# 4017Divider.net
KiCad netlist of a schematic drawn in EAGLE
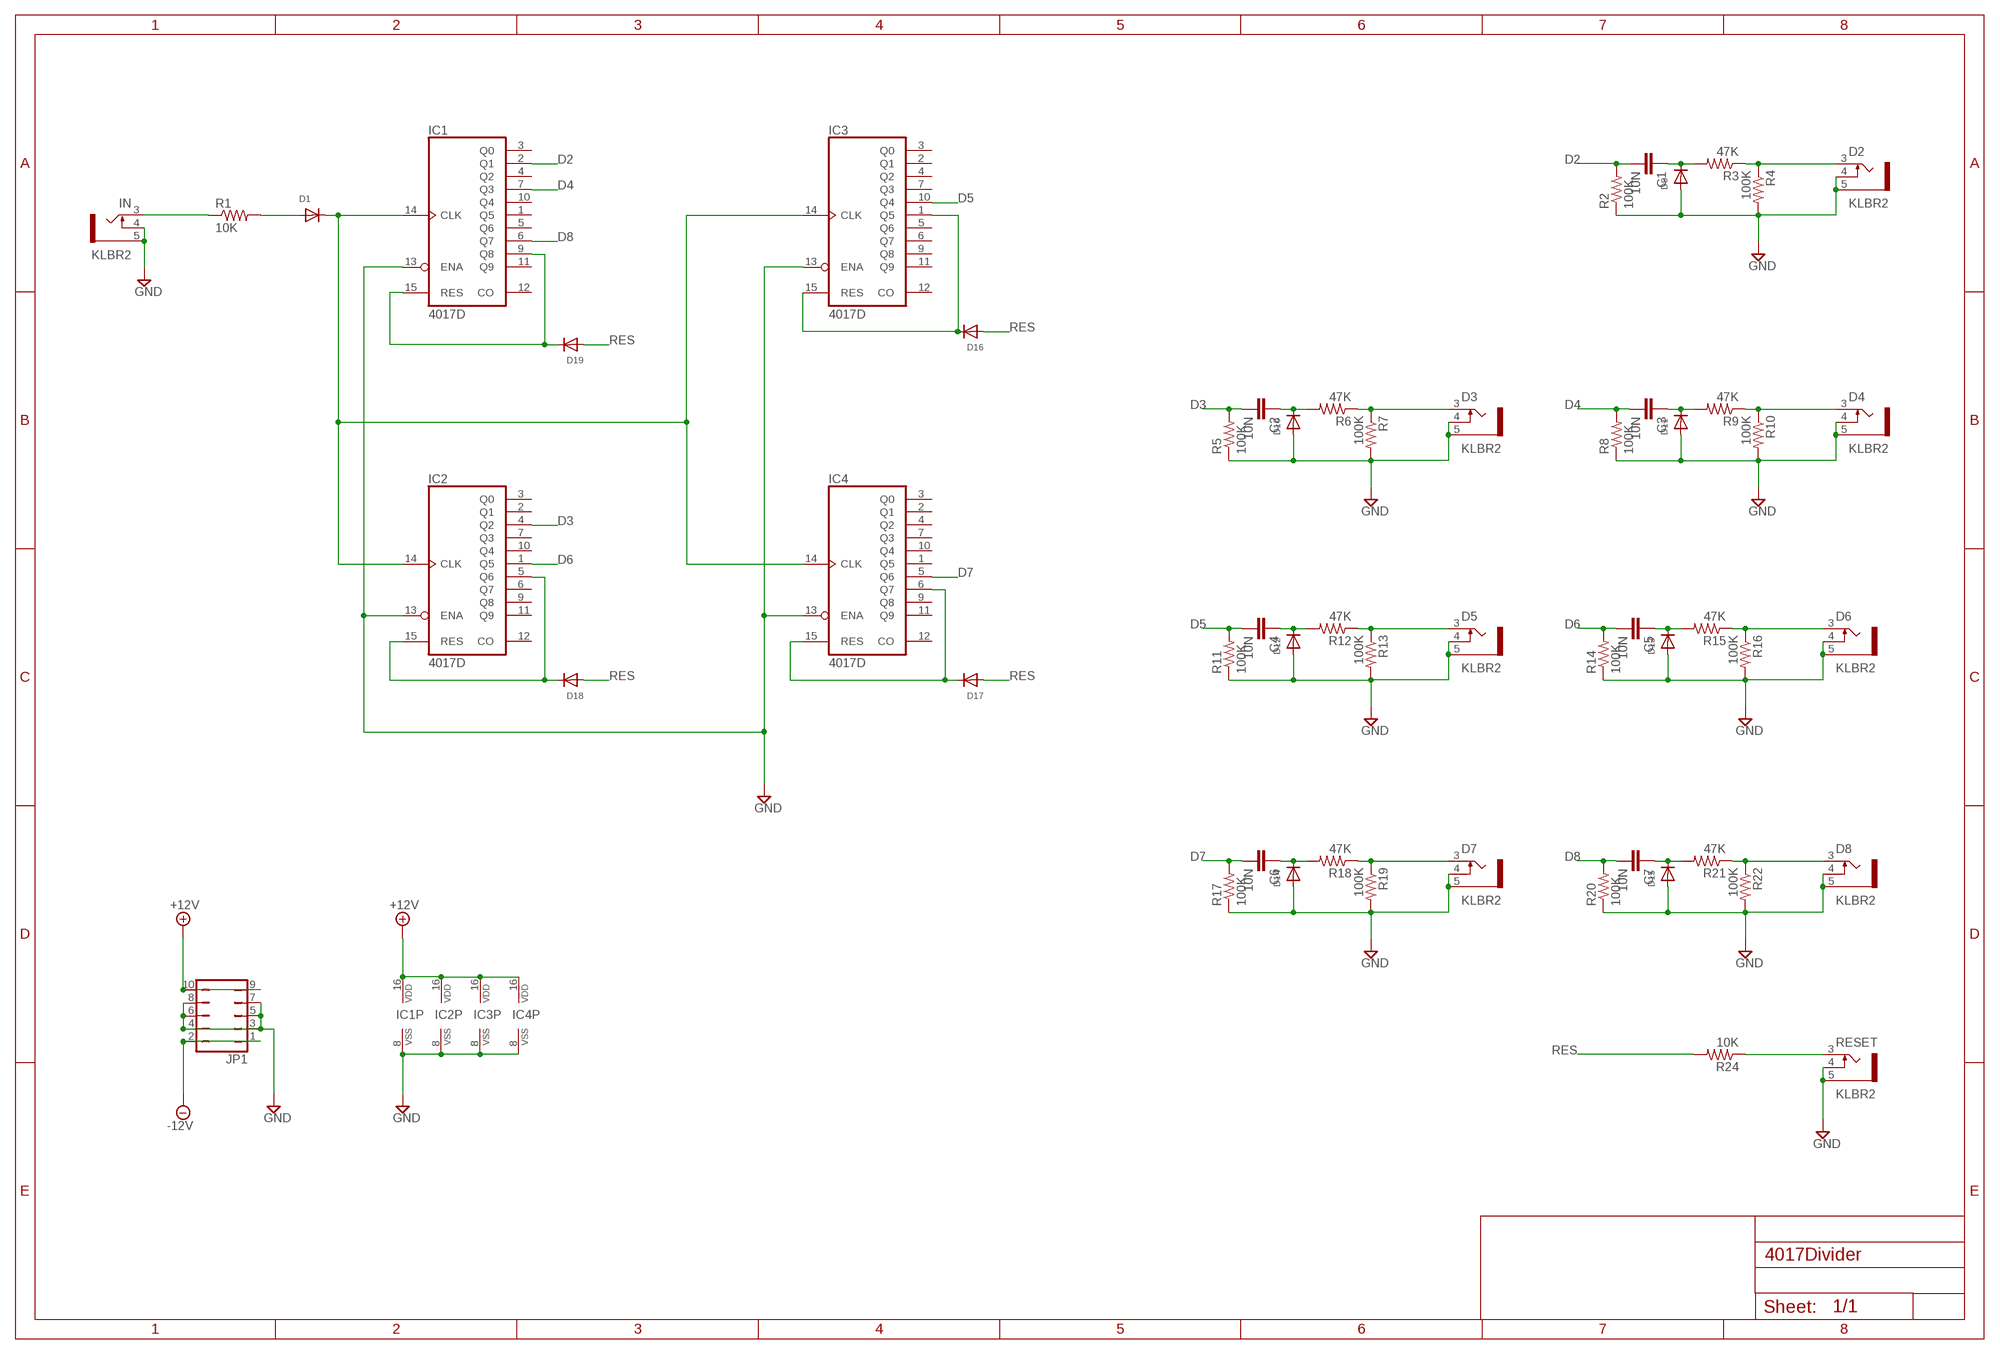
[diagram p0: schematic, sheet 1]

(export (version "E")
  (design (tool "Eeschema 10.0.6"))
  (components
    (comp (ref "C1")
      (value "10N")
      (footprint "eagle-import:C0603K")
      (libsource (lib "eagle-import") (part "C-EUC0603K"))
    )
    (comp (ref "C2")
      (value "10N")
      (footprint "eagle-import:C0603K")
      (libsource (lib "eagle-import") (part "C-EUC0603K"))
    )
    (comp (ref "C3")
      (value "10N")
      (footprint "eagle-import:C0603K")
      (libsource (lib "eagle-import") (part "C-EUC0603K"))
    )
    (comp (ref "C4")
      (value "10N")
      (footprint "eagle-import:C0603K")
      (libsource (lib "eagle-import") (part "C-EUC0603K"))
    )
    (comp (ref "C5")
      (value "10N")
      (footprint "eagle-import:C0603K")
      (libsource (lib "eagle-import") (part "C-EUC0603K"))
    )
    (comp (ref "C6")
      (value "10N")
      (footprint "eagle-import:C0603K")
      (libsource (lib "eagle-import") (part "C-EUC0603K"))
    )
    (comp (ref "C7")
      (value "10N")
      (footprint "eagle-import:C0603K")
      (libsource (lib "eagle-import") (part "C-EUC0603K"))
    )
    (comp (ref "D1")
      (value "DIODESOD-123")
      (footprint "eagle-import:SOD-123")
      (libsource (lib "eagle-import") (part "DIODESOD-123"))
    )
    (comp (ref "D2")
      (value "KLBR2")
      (footprint "eagle-import:KLBR2")
      (libsource (lib "eagle-import") (part "KLBR?2"))
    )
    (comp (ref "D3")
      (value "KLBR2")
      (footprint "eagle-import:KLBR2")
      (libsource (lib "eagle-import") (part "KLBR?2"))
    )
    (comp (ref "D4")
      (value "KLBR2")
      (footprint "eagle-import:KLBR2")
      (libsource (lib "eagle-import") (part "KLBR?2"))
    )
    (comp (ref "D5")
      (value "KLBR2")
      (footprint "eagle-import:KLBR2")
      (libsource (lib "eagle-import") (part "KLBR?2"))
    )
    (comp (ref "D6")
      (value "KLBR2")
      (footprint "eagle-import:KLBR2")
      (libsource (lib "eagle-import") (part "KLBR?2"))
    )
    (comp (ref "D7")
      (value "KLBR2")
      (footprint "eagle-import:KLBR2")
      (libsource (lib "eagle-import") (part "KLBR?2"))
    )
    (comp (ref "D8")
      (value "KLBR2")
      (footprint "eagle-import:KLBR2")
      (libsource (lib "eagle-import") (part "KLBR?2"))
    )
    (comp (ref "D9")
      (value "DIODESOD-123")
      (footprint "eagle-import:SOD-123")
      (libsource (lib "eagle-import") (part "DIODESOD-123"))
    )
    (comp (ref "D10")
      (value "DIODESOD-123")
      (footprint "eagle-import:SOD-123")
      (libsource (lib "eagle-import") (part "DIODESOD-123"))
    )
    (comp (ref "D11")
      (value "DIODESOD-123")
      (footprint "eagle-import:SOD-123")
      (libsource (lib "eagle-import") (part "DIODESOD-123"))
    )
    (comp (ref "D12")
      (value "DIODESOD-123")
      (footprint "eagle-import:SOD-123")
      (libsource (lib "eagle-import") (part "DIODESOD-123"))
    )
    (comp (ref "D13")
      (value "DIODESOD-123")
      (footprint "eagle-import:SOD-123")
      (libsource (lib "eagle-import") (part "DIODESOD-123"))
    )
    (comp (ref "D14")
      (value "DIODESOD-123")
      (footprint "eagle-import:SOD-123")
      (libsource (lib "eagle-import") (part "DIODESOD-123"))
    )
    (comp (ref "D15")
      (value "DIODESOD-123")
      (footprint "eagle-import:SOD-123")
      (libsource (lib "eagle-import") (part "DIODESOD-123"))
    )
    (comp (ref "D16")
      (value "DIODESOD-123")
      (footprint "eagle-import:SOD-123")
      (libsource (lib "eagle-import") (part "DIODESOD-123"))
    )
    (comp (ref "D17")
      (value "DIODESOD-123")
      (footprint "eagle-import:SOD-123")
      (libsource (lib "eagle-import") (part "DIODESOD-123"))
    )
    (comp (ref "D18")
      (value "DIODESOD-123")
      (footprint "eagle-import:SOD-123")
      (libsource (lib "eagle-import") (part "DIODESOD-123"))
    )
    (comp (ref "D19")
      (value "DIODESOD-123")
      (footprint "eagle-import:SOD-123")
      (libsource (lib "eagle-import") (part "DIODESOD-123"))
    )
    (comp (ref "IC1")
      (value "4017D")
      (footprint "eagle-import:SO16")
      (libsource (lib "eagle-import") (part "4017D"))
    )
    (comp (ref "IC2")
      (value "4017D")
      (footprint "eagle-import:SO16")
      (libsource (lib "eagle-import") (part "4017D"))
    )
    (comp (ref "IC3")
      (value "4017D")
      (footprint "eagle-import:SO16")
      (libsource (lib "eagle-import") (part "4017D"))
    )
    (comp (ref "IC4")
      (value "4017D")
      (footprint "eagle-import:SO16")
      (libsource (lib "eagle-import") (part "4017D"))
    )
    (comp (ref "IN")
      (value "KLBR2")
      (footprint "eagle-import:KLBR2")
      (libsource (lib "eagle-import") (part "KLBR?2"))
    )
    (comp (ref "JP1")
      (value "JP5Q")
      (footprint "eagle-import:JP5Q")
      (libsource (lib "eagle-import") (part "JP5Q"))
    )
    (comp (ref "R1")
      (value "10K")
      (footprint "eagle-import:R0603")
      (libsource (lib "eagle-import") (part "R-US_R0603"))
    )
    (comp (ref "R2")
      (value "100K")
      (footprint "eagle-import:R0603")
      (libsource (lib "eagle-import") (part "R-US_R0603"))
    )
    (comp (ref "R3")
      (value "47K")
      (footprint "eagle-import:R0603")
      (libsource (lib "eagle-import") (part "R-US_R0603"))
    )
    (comp (ref "R4")
      (value "100K")
      (footprint "eagle-import:R0603")
      (libsource (lib "eagle-import") (part "R-US_R0603"))
    )
    (comp (ref "R5")
      (value "100K")
      (footprint "eagle-import:R0603")
      (libsource (lib "eagle-import") (part "R-US_R0603"))
    )
    (comp (ref "R6")
      (value "47K")
      (footprint "eagle-import:R0603")
      (libsource (lib "eagle-import") (part "R-US_R0603"))
    )
    (comp (ref "R7")
      (value "100K")
      (footprint "eagle-import:R0603")
      (libsource (lib "eagle-import") (part "R-US_R0603"))
    )
    (comp (ref "R8")
      (value "100K")
      (footprint "eagle-import:R0603")
      (libsource (lib "eagle-import") (part "R-US_R0603"))
    )
    (comp (ref "R9")
      (value "47K")
      (footprint "eagle-import:R0603")
      (libsource (lib "eagle-import") (part "R-US_R0603"))
    )
    (comp (ref "R10")
      (value "100K")
      (footprint "eagle-import:R0603")
      (libsource (lib "eagle-import") (part "R-US_R0603"))
    )
    (comp (ref "R11")
      (value "100K")
      (footprint "eagle-import:R0603")
      (libsource (lib "eagle-import") (part "R-US_R0603"))
    )
    (comp (ref "R12")
      (value "47K")
      (footprint "eagle-import:R0603")
      (libsource (lib "eagle-import") (part "R-US_R0603"))
    )
    (comp (ref "R13")
      (value "100K")
      (footprint "eagle-import:R0603")
      (libsource (lib "eagle-import") (part "R-US_R0603"))
    )
    (comp (ref "R14")
      (value "100K")
      (footprint "eagle-import:R0603")
      (libsource (lib "eagle-import") (part "R-US_R0603"))
    )
    (comp (ref "R15")
      (value "47K")
      (footprint "eagle-import:R0603")
      (libsource (lib "eagle-import") (part "R-US_R0603"))
    )
    (comp (ref "R16")
      (value "100K")
      (footprint "eagle-import:R0603")
      (libsource (lib "eagle-import") (part "R-US_R0603"))
    )
    (comp (ref "R17")
      (value "100K")
      (footprint "eagle-import:R0603")
      (libsource (lib "eagle-import") (part "R-US_R0603"))
    )
    (comp (ref "R18")
      (value "47K")
      (footprint "eagle-import:R0603")
      (libsource (lib "eagle-import") (part "R-US_R0603"))
    )
    (comp (ref "R19")
      (value "100K")
      (footprint "eagle-import:R0603")
      (libsource (lib "eagle-import") (part "R-US_R0603"))
    )
    (comp (ref "R20")
      (value "100K")
      (footprint "eagle-import:R0603")
      (libsource (lib "eagle-import") (part "R-US_R0603"))
    )
    (comp (ref "R21")
      (value "47K")
      (footprint "eagle-import:R0603")
      (libsource (lib "eagle-import") (part "R-US_R0603"))
    )
    (comp (ref "R22")
      (value "100K")
      (footprint "eagle-import:R0603")
      (libsource (lib "eagle-import") (part "R-US_R0603"))
    )
    (comp (ref "R24")
      (value "10K")
      (footprint "eagle-import:R0603")
      (libsource (lib "eagle-import") (part "R-US_R0603"))
    )
    (comp (ref "RESET")
      (value "KLBR2")
      (footprint "eagle-import:KLBR2")
      (libsource (lib "eagle-import") (part "KLBR?2"))
    )
  )
  (nets
    (net (code "1") (name "+12V") (class "Default")
      (node (ref "IC1") (pin "16") (pinfunction "VDD_16") (pintype "power_in"))
      (node (ref "IC2") (pin "16") (pinfunction "VDD_16") (pintype "power_in"))
      (node (ref "IC3") (pin "16") (pinfunction "VDD_16") (pintype "power_in"))
      (node (ref "IC4") (pin "16") (pinfunction "VDD_16") (pintype "power_in"))
      (node (ref "JP1") (pin "10") (pinfunction "10_10") (pintype "passive"))
      (node (ref "JP1") (pin "9") (pinfunction "9_9") (pintype "passive"))
    )
    (net (code "2") (name "-12V") (class "Default")
      (node (ref "JP1") (pin "1") (pinfunction "1_1") (pintype "passive"))
      (node (ref "JP1") (pin "2") (pinfunction "2_2") (pintype "passive"))
    )
    (net (code "3") (name "/D2") (class "Default")
      (node (ref "C1") (pin "2") (pinfunction "2_2") (pintype "passive"))
      (node (ref "IC1") (pin "2") (pinfunction "Q1_2") (pintype "output"))
      (node (ref "R2") (pin "2") (pinfunction "2_2") (pintype "passive"))
    )
    (net (code "4") (name "/D3") (class "Default")
      (node (ref "C2") (pin "2") (pinfunction "2_2") (pintype "passive"))
      (node (ref "IC2") (pin "4") (pinfunction "Q2_4") (pintype "output"))
      (node (ref "R5") (pin "2") (pinfunction "2_2") (pintype "passive"))
    )
    (net (code "5") (name "/D4") (class "Default")
      (node (ref "C3") (pin "2") (pinfunction "2_2") (pintype "passive"))
      (node (ref "IC1") (pin "7") (pinfunction "Q3_7") (pintype "output"))
      (node (ref "R8") (pin "2") (pinfunction "2_2") (pintype "passive"))
    )
    (net (code "6") (name "/D5") (class "Default")
      (node (ref "C4") (pin "2") (pinfunction "2_2") (pintype "passive"))
      (node (ref "IC3") (pin "10") (pinfunction "Q4_10") (pintype "output"))
      (node (ref "R11") (pin "2") (pinfunction "2_2") (pintype "passive"))
    )
    (net (code "7") (name "/D6") (class "Default")
      (node (ref "C5") (pin "2") (pinfunction "2_2") (pintype "passive"))
      (node (ref "IC2") (pin "1") (pinfunction "Q5_1") (pintype "output"))
      (node (ref "R14") (pin "2") (pinfunction "2_2") (pintype "passive"))
    )
    (net (code "8") (name "/D7") (class "Default")
      (node (ref "C6") (pin "2") (pinfunction "2_2") (pintype "passive"))
      (node (ref "IC4") (pin "5") (pinfunction "Q6_5") (pintype "output"))
      (node (ref "R17") (pin "2") (pinfunction "2_2") (pintype "passive"))
    )
    (net (code "9") (name "/D8") (class "Default")
      (node (ref "C7") (pin "2") (pinfunction "2_2") (pintype "passive"))
      (node (ref "IC1") (pin "6") (pinfunction "Q7_6") (pintype "output"))
      (node (ref "R20") (pin "2") (pinfunction "2_2") (pintype "passive"))
    )
    (net (code "10") (name "/RES") (class "Default")
      (node (ref "D16") (pin "A") (pinfunction "A_A") (pintype "passive"))
      (node (ref "D17") (pin "A") (pinfunction "A_A") (pintype "passive"))
      (node (ref "D18") (pin "A") (pinfunction "A_A") (pintype "passive"))
      (node (ref "D19") (pin "A") (pinfunction "A_A") (pintype "passive"))
      (node (ref "R24") (pin "2") (pinfunction "2_2") (pintype "passive"))
    )
    (net (code "11") (name "GND") (class "Default")
      (node (ref "D10") (pin "A") (pinfunction "A_A") (pintype "passive"))
      (node (ref "D11") (pin "A") (pinfunction "A_A") (pintype "passive"))
      (node (ref "D12") (pin "A") (pinfunction "A_A") (pintype "passive"))
      (node (ref "D13") (pin "A") (pinfunction "A_A") (pintype "passive"))
      (node (ref "D14") (pin "A") (pinfunction "A_A") (pintype "passive"))
      (node (ref "D15") (pin "A") (pinfunction "A_A") (pintype "passive"))
      (node (ref "D2") (pin "4") (pinfunction "4_4") (pintype "passive"))
      (node (ref "D2") (pin "5") (pinfunction "5_5") (pintype "passive"))
      (node (ref "D3") (pin "4") (pinfunction "4_4") (pintype "passive"))
      (node (ref "D3") (pin "5") (pinfunction "5_5") (pintype "passive"))
      (node (ref "D4") (pin "4") (pinfunction "4_4") (pintype "passive"))
      (node (ref "D4") (pin "5") (pinfunction "5_5") (pintype "passive"))
      (node (ref "D5") (pin "4") (pinfunction "4_4") (pintype "passive"))
      (node (ref "D5") (pin "5") (pinfunction "5_5") (pintype "passive"))
      (node (ref "D6") (pin "4") (pinfunction "4_4") (pintype "passive"))
      (node (ref "D6") (pin "5") (pinfunction "5_5") (pintype "passive"))
      (node (ref "D7") (pin "4") (pinfunction "4_4") (pintype "passive"))
      (node (ref "D7") (pin "5") (pinfunction "5_5") (pintype "passive"))
      (node (ref "D8") (pin "4") (pinfunction "4_4") (pintype "passive"))
      (node (ref "D8") (pin "5") (pinfunction "5_5") (pintype "passive"))
      (node (ref "D9") (pin "A") (pinfunction "A_A") (pintype "passive"))
      (node (ref "IC1") (pin "13") (pinfunction "ENA_13") (pintype "input"))
      (node (ref "IC1") (pin "8") (pinfunction "VSS_8") (pintype "power_in"))
      (node (ref "IC2") (pin "13") (pinfunction "ENA_13") (pintype "input"))
      (node (ref "IC2") (pin "8") (pinfunction "VSS_8") (pintype "power_in"))
      (node (ref "IC3") (pin "13") (pinfunction "ENA_13") (pintype "input"))
      (node (ref "IC3") (pin "8") (pinfunction "VSS_8") (pintype "power_in"))
      (node (ref "IC4") (pin "13") (pinfunction "ENA_13") (pintype "input"))
      (node (ref "IC4") (pin "8") (pinfunction "VSS_8") (pintype "power_in"))
      (node (ref "IN") (pin "4") (pinfunction "4_4") (pintype "passive"))
      (node (ref "IN") (pin "5") (pinfunction "5_5") (pintype "passive"))
      (node (ref "JP1") (pin "3") (pinfunction "3_3") (pintype "passive"))
      (node (ref "JP1") (pin "4") (pinfunction "4_4") (pintype "passive"))
      (node (ref "JP1") (pin "5") (pinfunction "5_5") (pintype "passive"))
      (node (ref "JP1") (pin "6") (pinfunction "6_6") (pintype "passive"))
      (node (ref "JP1") (pin "7") (pinfunction "7_7") (pintype "passive"))
      (node (ref "JP1") (pin "8") (pinfunction "8_8") (pintype "passive"))
      (node (ref "R10") (pin "2") (pinfunction "2_2") (pintype "passive"))
      (node (ref "R11") (pin "1") (pinfunction "1_1") (pintype "passive"))
      (node (ref "R13") (pin "2") (pinfunction "2_2") (pintype "passive"))
      (node (ref "R14") (pin "1") (pinfunction "1_1") (pintype "passive"))
      (node (ref "R16") (pin "2") (pinfunction "2_2") (pintype "passive"))
      (node (ref "R17") (pin "1") (pinfunction "1_1") (pintype "passive"))
      (node (ref "R19") (pin "2") (pinfunction "2_2") (pintype "passive"))
      (node (ref "R2") (pin "1") (pinfunction "1_1") (pintype "passive"))
      (node (ref "R20") (pin "1") (pinfunction "1_1") (pintype "passive"))
      (node (ref "R22") (pin "2") (pinfunction "2_2") (pintype "passive"))
      (node (ref "R4") (pin "2") (pinfunction "2_2") (pintype "passive"))
      (node (ref "R5") (pin "1") (pinfunction "1_1") (pintype "passive"))
      (node (ref "R7") (pin "2") (pinfunction "2_2") (pintype "passive"))
      (node (ref "R8") (pin "1") (pinfunction "1_1") (pintype "passive"))
      (node (ref "RESET") (pin "4") (pinfunction "4_4") (pintype "passive"))
      (node (ref "RESET") (pin "5") (pinfunction "5_5") (pintype "passive"))
    )
    (net (code "12") (name "Net-(C1-Pad1)") (class "Default")
      (node (ref "C1") (pin "1") (pinfunction "1_1") (pintype "passive"))
      (node (ref "D9") (pin "C") (pinfunction "C_C") (pintype "passive"))
      (node (ref "R3") (pin "2") (pinfunction "2_2") (pintype "passive"))
    )
    (net (code "13") (name "Net-(C2-Pad1)") (class "Default")
      (node (ref "C2") (pin "1") (pinfunction "1_1") (pintype "passive"))
      (node (ref "D10") (pin "C") (pinfunction "C_C") (pintype "passive"))
      (node (ref "R6") (pin "2") (pinfunction "2_2") (pintype "passive"))
    )
    (net (code "14") (name "Net-(C3-Pad1)") (class "Default")
      (node (ref "C3") (pin "1") (pinfunction "1_1") (pintype "passive"))
      (node (ref "D11") (pin "C") (pinfunction "C_C") (pintype "passive"))
      (node (ref "R9") (pin "2") (pinfunction "2_2") (pintype "passive"))
    )
    (net (code "15") (name "Net-(C4-Pad1)") (class "Default")
      (node (ref "C4") (pin "1") (pinfunction "1_1") (pintype "passive"))
      (node (ref "D12") (pin "C") (pinfunction "C_C") (pintype "passive"))
      (node (ref "R12") (pin "2") (pinfunction "2_2") (pintype "passive"))
    )
    (net (code "16") (name "Net-(C5-Pad1)") (class "Default")
      (node (ref "C5") (pin "1") (pinfunction "1_1") (pintype "passive"))
      (node (ref "D13") (pin "C") (pinfunction "C_C") (pintype "passive"))
      (node (ref "R15") (pin "2") (pinfunction "2_2") (pintype "passive"))
    )
    (net (code "17") (name "Net-(C6-Pad1)") (class "Default")
      (node (ref "C6") (pin "1") (pinfunction "1_1") (pintype "passive"))
      (node (ref "D14") (pin "C") (pinfunction "C_C") (pintype "passive"))
      (node (ref "R18") (pin "2") (pinfunction "2_2") (pintype "passive"))
    )
    (net (code "18") (name "Net-(C7-Pad1)") (class "Default")
      (node (ref "C7") (pin "1") (pinfunction "1_1") (pintype "passive"))
      (node (ref "D15") (pin "C") (pinfunction "C_C") (pintype "passive"))
      (node (ref "R21") (pin "2") (pinfunction "2_2") (pintype "passive"))
    )
    (net (code "19") (name "Net-(D1-PadA)") (class "Default")
      (node (ref "D1") (pin "A") (pinfunction "A_A") (pintype "passive"))
      (node (ref "R1") (pin "2") (pinfunction "2_2") (pintype "passive"))
    )
    (net (code "20") (name "Net-(D2-Pad3)") (class "Default")
      (node (ref "D2") (pin "3") (pinfunction "3_3") (pintype "passive"))
      (node (ref "R3") (pin "1") (pinfunction "1_1") (pintype "passive"))
      (node (ref "R4") (pin "1") (pinfunction "1_1") (pintype "passive"))
    )
    (net (code "21") (name "Net-(D3-Pad3)") (class "Default")
      (node (ref "D3") (pin "3") (pinfunction "3_3") (pintype "passive"))
      (node (ref "R6") (pin "1") (pinfunction "1_1") (pintype "passive"))
      (node (ref "R7") (pin "1") (pinfunction "1_1") (pintype "passive"))
    )
    (net (code "22") (name "Net-(D4-Pad3)") (class "Default")
      (node (ref "D4") (pin "3") (pinfunction "3_3") (pintype "passive"))
      (node (ref "R10") (pin "1") (pinfunction "1_1") (pintype "passive"))
      (node (ref "R9") (pin "1") (pinfunction "1_1") (pintype "passive"))
    )
    (net (code "23") (name "Net-(D5-Pad3)") (class "Default")
      (node (ref "D5") (pin "3") (pinfunction "3_3") (pintype "passive"))
      (node (ref "R12") (pin "1") (pinfunction "1_1") (pintype "passive"))
      (node (ref "R13") (pin "1") (pinfunction "1_1") (pintype "passive"))
    )
    (net (code "24") (name "Net-(D6-Pad3)") (class "Default")
      (node (ref "D6") (pin "3") (pinfunction "3_3") (pintype "passive"))
      (node (ref "R15") (pin "1") (pinfunction "1_1") (pintype "passive"))
      (node (ref "R16") (pin "1") (pinfunction "1_1") (pintype "passive"))
    )
    (net (code "25") (name "Net-(D7-Pad3)") (class "Default")
      (node (ref "D7") (pin "3") (pinfunction "3_3") (pintype "passive"))
      (node (ref "R18") (pin "1") (pinfunction "1_1") (pintype "passive"))
      (node (ref "R19") (pin "1") (pinfunction "1_1") (pintype "passive"))
    )
    (net (code "26") (name "Net-(D8-Pad3)") (class "Default")
      (node (ref "D8") (pin "3") (pinfunction "3_3") (pintype "passive"))
      (node (ref "R21") (pin "1") (pinfunction "1_1") (pintype "passive"))
      (node (ref "R22") (pin "1") (pinfunction "1_1") (pintype "passive"))
    )
    (net (code "27") (name "Net-(IC1A-CLK)") (class "Default")
      (node (ref "D1") (pin "C") (pinfunction "C_C") (pintype "passive"))
      (node (ref "IC1") (pin "14") (pinfunction "CLK_14") (pintype "input"))
      (node (ref "IC2") (pin "14") (pinfunction "CLK_14") (pintype "input"))
      (node (ref "IC3") (pin "14") (pinfunction "CLK_14") (pintype "input"))
      (node (ref "IC4") (pin "14") (pinfunction "CLK_14") (pintype "input"))
    )
    (net (code "28") (name "Net-(IC1A-Q8)") (class "Default")
      (node (ref "D19") (pin "C") (pinfunction "C_C") (pintype "passive"))
      (node (ref "IC1") (pin "15") (pinfunction "RES_15") (pintype "input"))
      (node (ref "IC1") (pin "9") (pinfunction "Q8_9") (pintype "output"))
    )
    (net (code "29") (name "Net-(IC2A-Q6)") (class "Default")
      (node (ref "D18") (pin "C") (pinfunction "C_C") (pintype "passive"))
      (node (ref "IC2") (pin "15") (pinfunction "RES_15") (pintype "input"))
      (node (ref "IC2") (pin "5") (pinfunction "Q6_5") (pintype "output"))
    )
    (net (code "30") (name "Net-(IC3A-Q5)") (class "Default")
      (node (ref "D16") (pin "C") (pinfunction "C_C") (pintype "passive"))
      (node (ref "IC3") (pin "1") (pinfunction "Q5_1") (pintype "output"))
      (node (ref "IC3") (pin "15") (pinfunction "RES_15") (pintype "input"))
    )
    (net (code "31") (name "Net-(IC4A-Q7)") (class "Default")
      (node (ref "D17") (pin "C") (pinfunction "C_C") (pintype "passive"))
      (node (ref "IC4") (pin "15") (pinfunction "RES_15") (pintype "input"))
      (node (ref "IC4") (pin "6") (pinfunction "Q7_6") (pintype "output"))
    )
    (net (code "32") (name "Net-(IN-Pad3)") (class "Default")
      (node (ref "IN") (pin "3") (pinfunction "3_3") (pintype "passive"))
      (node (ref "R1") (pin "1") (pinfunction "1_1") (pintype "passive"))
    )
    (net (code "33") (name "Net-(R24-Pad1)") (class "Default")
      (node (ref "R24") (pin "1") (pinfunction "1_1") (pintype "passive"))
      (node (ref "RESET") (pin "3") (pinfunction "3_3") (pintype "passive"))
    )
    (net (code "34") (name "unconnected-(IC1A-CO-Pad12)") (class "Default")
      (node (ref "IC1") (pin "12") (pinfunction "CO_12") (pintype "output"))
    )
    (net (code "35") (name "unconnected-(IC1A-Q0-Pad3)") (class "Default")
      (node (ref "IC1") (pin "3") (pinfunction "Q0_3") (pintype "output"))
    )
    (net (code "36") (name "unconnected-(IC1A-Q2-Pad4)") (class "Default")
      (node (ref "IC1") (pin "4") (pinfunction "Q2_4") (pintype "output"))
    )
    (net (code "37") (name "unconnected-(IC1A-Q4-Pad10)") (class "Default")
      (node (ref "IC1") (pin "10") (pinfunction "Q4_10") (pintype "output"))
    )
    (net (code "38") (name "unconnected-(IC1A-Q5-Pad1)") (class "Default")
      (node (ref "IC1") (pin "1") (pinfunction "Q5_1") (pintype "output"))
    )
    (net (code "39") (name "unconnected-(IC1A-Q6-Pad5)") (class "Default")
      (node (ref "IC1") (pin "5") (pinfunction "Q6_5") (pintype "output"))
    )
    (net (code "40") (name "unconnected-(IC1A-Q9-Pad11)") (class "Default")
      (node (ref "IC1") (pin "11") (pinfunction "Q9_11") (pintype "output"))
    )
    (net (code "41") (name "unconnected-(IC2A-CO-Pad12)") (class "Default")
      (node (ref "IC2") (pin "12") (pinfunction "CO_12") (pintype "output"))
    )
    (net (code "42") (name "unconnected-(IC2A-Q0-Pad3)") (class "Default")
      (node (ref "IC2") (pin "3") (pinfunction "Q0_3") (pintype "output"))
    )
    (net (code "43") (name "unconnected-(IC2A-Q1-Pad2)") (class "Default")
      (node (ref "IC2") (pin "2") (pinfunction "Q1_2") (pintype "output"))
    )
    (net (code "44") (name "unconnected-(IC2A-Q3-Pad7)") (class "Default")
      (node (ref "IC2") (pin "7") (pinfunction "Q3_7") (pintype "output"))
    )
    (net (code "45") (name "unconnected-(IC2A-Q4-Pad10)") (class "Default")
      (node (ref "IC2") (pin "10") (pinfunction "Q4_10") (pintype "output"))
    )
    (net (code "46") (name "unconnected-(IC2A-Q7-Pad6)") (class "Default")
      (node (ref "IC2") (pin "6") (pinfunction "Q7_6") (pintype "output"))
    )
    (net (code "47") (name "unconnected-(IC2A-Q8-Pad9)") (class "Default")
      (node (ref "IC2") (pin "9") (pinfunction "Q8_9") (pintype "output"))
    )
    (net (code "48") (name "unconnected-(IC2A-Q9-Pad11)") (class "Default")
      (node (ref "IC2") (pin "11") (pinfunction "Q9_11") (pintype "output"))
    )
    (net (code "49") (name "unconnected-(IC3A-CO-Pad12)") (class "Default")
      (node (ref "IC3") (pin "12") (pinfunction "CO_12") (pintype "output"))
    )
    (net (code "50") (name "unconnected-(IC3A-Q0-Pad3)") (class "Default")
      (node (ref "IC3") (pin "3") (pinfunction "Q0_3") (pintype "output"))
    )
    (net (code "51") (name "unconnected-(IC3A-Q1-Pad2)") (class "Default")
      (node (ref "IC3") (pin "2") (pinfunction "Q1_2") (pintype "output"))
    )
    (net (code "52") (name "unconnected-(IC3A-Q2-Pad4)") (class "Default")
      (node (ref "IC3") (pin "4") (pinfunction "Q2_4") (pintype "output"))
    )
    (net (code "53") (name "unconnected-(IC3A-Q3-Pad7)") (class "Default")
      (node (ref "IC3") (pin "7") (pinfunction "Q3_7") (pintype "output"))
    )
    (net (code "54") (name "unconnected-(IC3A-Q6-Pad5)") (class "Default")
      (node (ref "IC3") (pin "5") (pinfunction "Q6_5") (pintype "output"))
    )
    (net (code "55") (name "unconnected-(IC3A-Q7-Pad6)") (class "Default")
      (node (ref "IC3") (pin "6") (pinfunction "Q7_6") (pintype "output"))
    )
    (net (code "56") (name "unconnected-(IC3A-Q8-Pad9)") (class "Default")
      (node (ref "IC3") (pin "9") (pinfunction "Q8_9") (pintype "output"))
    )
    (net (code "57") (name "unconnected-(IC3A-Q9-Pad11)") (class "Default")
      (node (ref "IC3") (pin "11") (pinfunction "Q9_11") (pintype "output"))
    )
    (net (code "58") (name "unconnected-(IC4A-CO-Pad12)") (class "Default")
      (node (ref "IC4") (pin "12") (pinfunction "CO_12") (pintype "output"))
    )
    (net (code "59") (name "unconnected-(IC4A-Q0-Pad3)") (class "Default")
      (node (ref "IC4") (pin "3") (pinfunction "Q0_3") (pintype "output"))
    )
    (net (code "60") (name "unconnected-(IC4A-Q1-Pad2)") (class "Default")
      (node (ref "IC4") (pin "2") (pinfunction "Q1_2") (pintype "output"))
    )
    (net (code "61") (name "unconnected-(IC4A-Q2-Pad4)") (class "Default")
      (node (ref "IC4") (pin "4") (pinfunction "Q2_4") (pintype "output"))
    )
    (net (code "62") (name "unconnected-(IC4A-Q3-Pad7)") (class "Default")
      (node (ref "IC4") (pin "7") (pinfunction "Q3_7") (pintype "output"))
    )
    (net (code "63") (name "unconnected-(IC4A-Q4-Pad10)") (class "Default")
      (node (ref "IC4") (pin "10") (pinfunction "Q4_10") (pintype "output"))
    )
    (net (code "64") (name "unconnected-(IC4A-Q5-Pad1)") (class "Default")
      (node (ref "IC4") (pin "1") (pinfunction "Q5_1") (pintype "output"))
    )
    (net (code "65") (name "unconnected-(IC4A-Q8-Pad9)") (class "Default")
      (node (ref "IC4") (pin "9") (pinfunction "Q8_9") (pintype "output"))
    )
    (net (code "66") (name "unconnected-(IC4A-Q9-Pad11)") (class "Default")
      (node (ref "IC4") (pin "11") (pinfunction "Q9_11") (pintype "output"))
    )
  )
)
